# v3_0_0_programmer.net
KiCad netlist of a schematic drawn in EAGLE
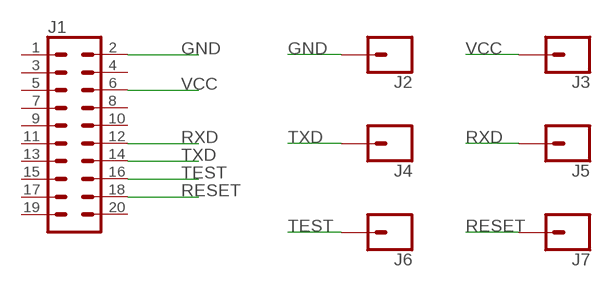
[diagram p0: schematic, sheet 1]

(export (version "E")
  (design (tool "Eeschema 10.0.6"))
  (components
    (comp (ref "J1")
      (value "CONN_10X2NOSILK")
      (footprint "eagle-import:2X10_NOSILK")
      (libsource (lib "eagle-import") (part "CONN_10X2NOSILK"))
    )
    (comp (ref "J2")
      (value "CONN_01")
      (footprint "eagle-import:1X01")
      (libsource (lib "eagle-import") (part "CONN_01"))
    )
    (comp (ref "J3")
      (value "CONN_01")
      (footprint "eagle-import:1X01")
      (libsource (lib "eagle-import") (part "CONN_01"))
    )
    (comp (ref "J4")
      (value "CONN_01")
      (footprint "eagle-import:1X01")
      (libsource (lib "eagle-import") (part "CONN_01"))
    )
    (comp (ref "J5")
      (value "CONN_01")
      (footprint "eagle-import:1X01")
      (libsource (lib "eagle-import") (part "CONN_01"))
    )
    (comp (ref "J6")
      (value "CONN_01")
      (footprint "eagle-import:1X01")
      (libsource (lib "eagle-import") (part "CONN_01"))
    )
    (comp (ref "J7")
      (value "CONN_01")
      (footprint "eagle-import:1X01")
      (libsource (lib "eagle-import") (part "CONN_01"))
    )
  )
  (nets
    (net (code "1") (name "/GND") (class "Default")
      (node (ref "J1") (pin "2") (pinfunction "2_2") (pintype "passive"))
      (node (ref "J2") (pin "1") (pinfunction "1_1") (pintype "passive"))
    )
    (net (code "2") (name "/RESET") (class "Default")
      (node (ref "J1") (pin "18") (pinfunction "18_18") (pintype "passive"))
      (node (ref "J7") (pin "1") (pinfunction "1_1") (pintype "passive"))
    )
    (net (code "3") (name "/RXD") (class "Default")
      (node (ref "J1") (pin "12") (pinfunction "12_12") (pintype "passive"))
      (node (ref "J5") (pin "1") (pinfunction "1_1") (pintype "passive"))
    )
    (net (code "4") (name "/TEST") (class "Default")
      (node (ref "J1") (pin "16") (pinfunction "16_16") (pintype "passive"))
      (node (ref "J6") (pin "1") (pinfunction "1_1") (pintype "passive"))
    )
    (net (code "5") (name "/TXD") (class "Default")
      (node (ref "J1") (pin "14") (pinfunction "14_14") (pintype "passive"))
      (node (ref "J4") (pin "1") (pinfunction "1_1") (pintype "passive"))
    )
    (net (code "6") (name "/VCC") (class "Default")
      (node (ref "J1") (pin "6") (pinfunction "6_6") (pintype "passive"))
      (node (ref "J3") (pin "1") (pinfunction "1_1") (pintype "passive"))
    )
    (net (code "7") (name "unconnected-(J1-Pad1)") (class "Default")
      (node (ref "J1") (pin "1") (pinfunction "1_1") (pintype "passive"))
    )
    (net (code "8") (name "unconnected-(J1-Pad3)") (class "Default")
      (node (ref "J1") (pin "3") (pinfunction "3_3") (pintype "passive"))
    )
    (net (code "9") (name "unconnected-(J1-Pad4)") (class "Default")
      (node (ref "J1") (pin "4") (pinfunction "4_4") (pintype "passive"))
    )
    (net (code "10") (name "unconnected-(J1-Pad5)") (class "Default")
      (node (ref "J1") (pin "5") (pinfunction "5_5") (pintype "passive"))
    )
    (net (code "11") (name "unconnected-(J1-Pad7)") (class "Default")
      (node (ref "J1") (pin "7") (pinfunction "7_7") (pintype "passive"))
    )
    (net (code "12") (name "unconnected-(J1-Pad8)") (class "Default")
      (node (ref "J1") (pin "8") (pinfunction "8_8") (pintype "passive"))
    )
    (net (code "13") (name "unconnected-(J1-Pad9)") (class "Default")
      (node (ref "J1") (pin "9") (pinfunction "9_9") (pintype "passive"))
    )
    (net (code "14") (name "unconnected-(J1-Pad10)") (class "Default")
      (node (ref "J1") (pin "10") (pinfunction "10_10") (pintype "passive"))
    )
    (net (code "15") (name "unconnected-(J1-Pad11)") (class "Default")
      (node (ref "J1") (pin "11") (pinfunction "11_11") (pintype "passive"))
    )
    (net (code "16") (name "unconnected-(J1-Pad13)") (class "Default")
      (node (ref "J1") (pin "13") (pinfunction "13_13") (pintype "passive"))
    )
    (net (code "17") (name "unconnected-(J1-Pad15)") (class "Default")
      (node (ref "J1") (pin "15") (pinfunction "15_15") (pintype "passive"))
    )
    (net (code "18") (name "unconnected-(J1-Pad17)") (class "Default")
      (node (ref "J1") (pin "17") (pinfunction "17_17") (pintype "passive"))
    )
    (net (code "19") (name "unconnected-(J1-Pad19)") (class "Default")
      (node (ref "J1") (pin "19") (pinfunction "19_19") (pintype "passive"))
    )
    (net (code "20") (name "unconnected-(J1-Pad20)") (class "Default")
      (node (ref "J1") (pin "20") (pinfunction "20_20") (pintype "passive"))
    )
  )
)
